# Trail-Traffic-Counter-Board-v10.net
KiCad netlist of a schematic drawn in EAGLE
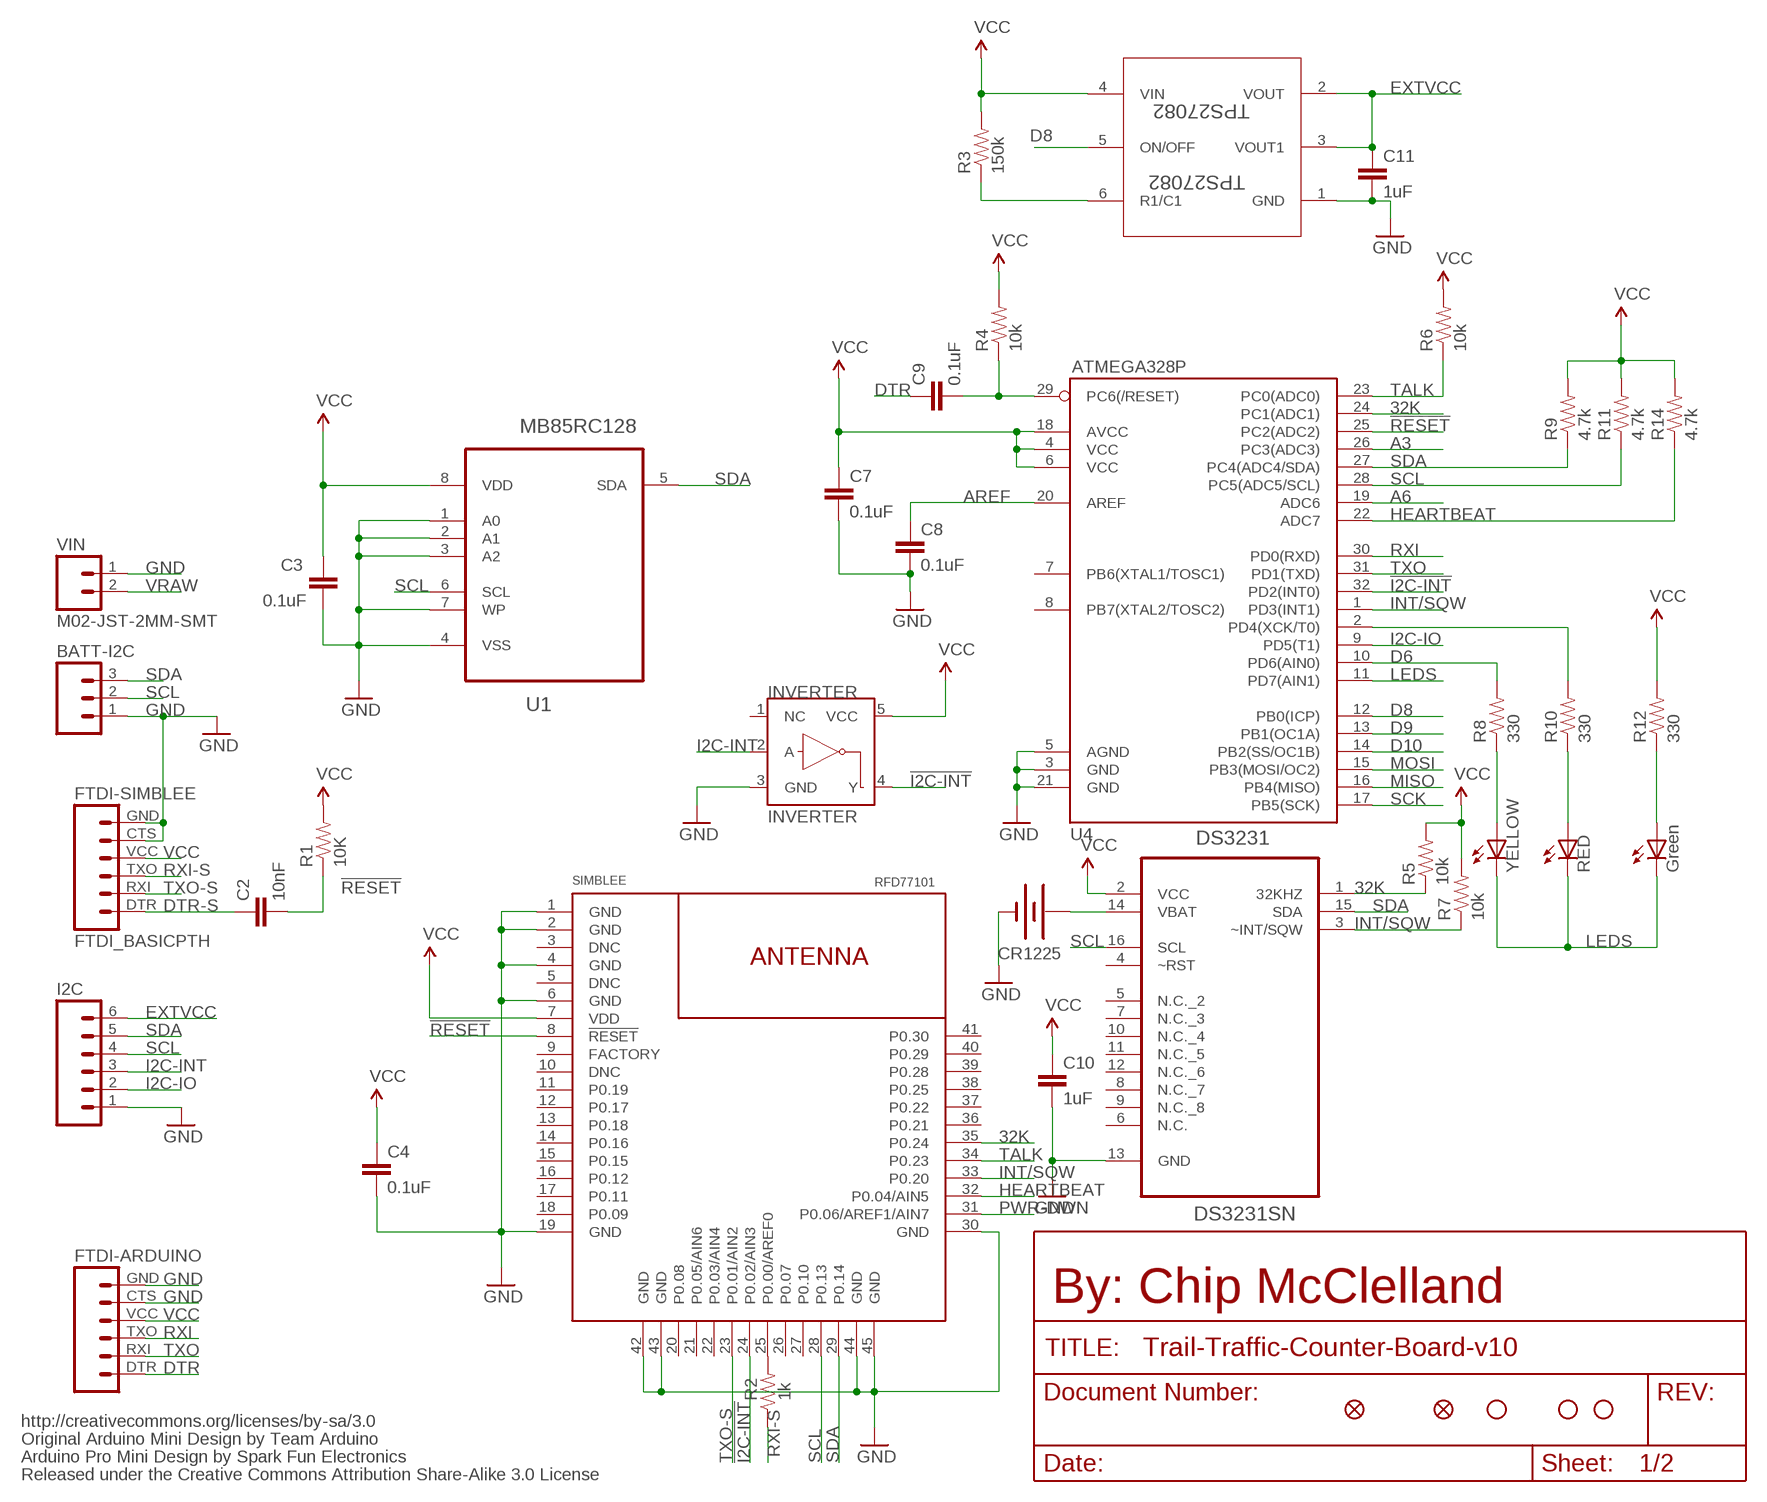
[diagram p0: schematic, sheet 1]
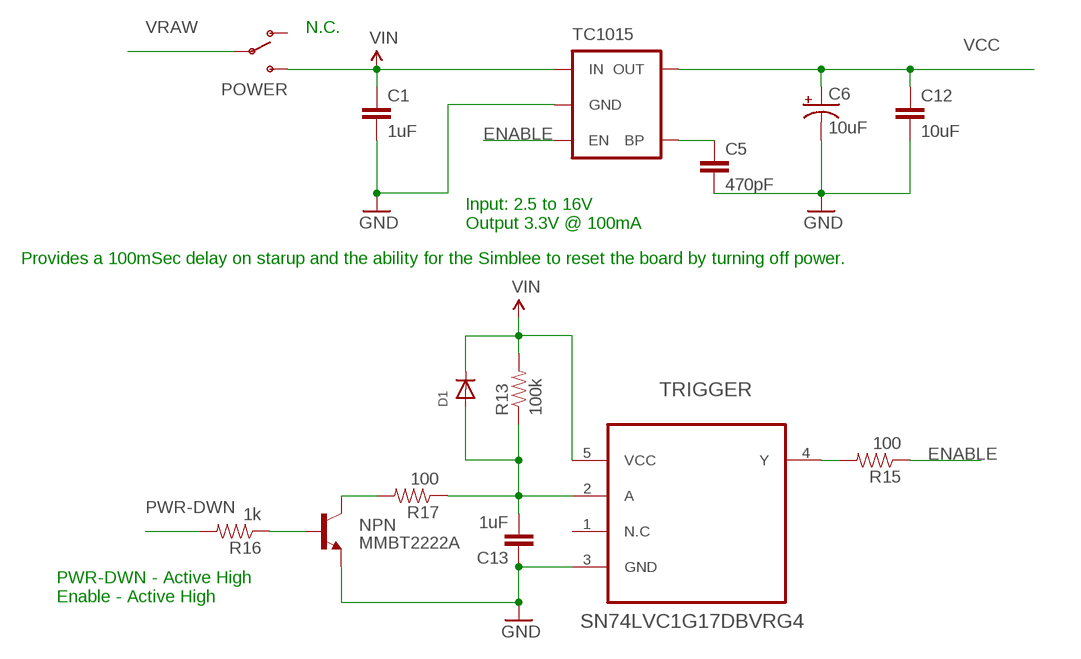
[diagram p1: schematic, sheet 2]

(export (version "E")
  (design (tool "Eeschema 10.0.6"))
  (components
    (comp (ref "C1")
      (value "1uF")
      (footprint "eagle-import:0805")
      (libsource (lib "eagle-import") (part "SparkFun-Passives_CAP0805"))
    )
    (comp (ref "C5")
      (value "470pF")
      (footprint "eagle-import:0805")
      (libsource (lib "eagle-import") (part "SparkFun-Passives_CAP0805"))
    )
    (comp (ref "C6")
      (value "10uF")
      (footprint "eagle-import:EIA3216")
      (libsource (lib "eagle-import") (part "CAP_POL1206"))
    )
    (comp (ref "C12")
      (value "10uF")
      (footprint "eagle-import:0805")
      (libsource (lib "eagle-import") (part "SparkFun-Passives_CAP0805"))
    )
    (comp (ref "C13")
      (value "1uF")
      (footprint "eagle-import:0805")
      (libsource (lib "eagle-import") (part "CAP0805"))
    )
    (comp (ref "D1")
      (value "DIODESOD-523")
      (footprint "eagle-import:SOD-523")
      (libsource (lib "eagle-import") (part "DIODESOD-523"))
    )
    (comp (ref "NPN")
      (value "MMBT2222A")
      (footprint "eagle-import:SOT23-3")
      (libsource (lib "eagle-import") (part "TRANSISTOR_NPNMMBT2222A"))
    )
    (comp (ref "POWER")
      (value "SWITCH-SPDTPTH")
      (footprint "eagle-import:SWITCH-SPDT")
      (libsource (lib "eagle-import") (part "SWITCH-SPDTPTH"))
    )
    (comp (ref "R13")
      (value "100k")
      (footprint "eagle-import:0805")
      (libsource (lib "eagle-import") (part "RESISTOR0805-RES"))
    )
    (comp (ref "R15")
      (value "100")
      (footprint "eagle-import:0805")
      (libsource (lib "eagle-import") (part "RESISTOR0805-RES"))
    )
    (comp (ref "R16")
      (value "1k")
      (footprint "eagle-import:0805")
      (libsource (lib "eagle-import") (part "RESISTOR0805-RES"))
    )
    (comp (ref "R17")
      (value "100")
      (footprint "eagle-import:0805")
      (libsource (lib "eagle-import") (part "RESISTOR0805-RES"))
    )
    (comp (ref "TC1015")
      (value "MIC52053.3V")
      (footprint "eagle-import:SOT23-5")
      (libsource (lib "eagle-import") (part "MIC52053.3V"))
    )
    (comp (ref "TRIGGER")
      (value "SN74LVC1G17DBVRG4")
      (footprint "eagle-import:SOT95P280X145-5N")
      (libsource (lib "eagle-import") (part "SN74LVC1G17DBVRG4"))
    )
    (comp (ref "ATMEGA328P")
      (value "U4")
      (footprint "eagle-import:TQFP32-08")
      (libsource (lib "eagle-import") (part "ATMEGA168"))
    )
    (comp (ref "BATT-I2C")
      (value "M03LOCK")
      (footprint "eagle-import:1X03_LOCK")
      (libsource (lib "eagle-import") (part "M03LOCK"))
    )
    (comp (ref "C2")
      (value "10nF")
      (footprint "eagle-import:0805")
      (libsource (lib "eagle-import") (part "SparkFun-Passives_CAP0805"))
    )
    (comp (ref "C3")
      (value "0.1uF")
      (footprint "eagle-import:0805")
      (libsource (lib "eagle-import") (part "CAP0805"))
    )
    (comp (ref "C4")
      (value "0.1uF")
      (footprint "eagle-import:0805")
      (libsource (lib "eagle-import") (part "CAP0805"))
    )
    (comp (ref "C7")
      (value "0.1uF")
      (footprint "eagle-import:0805")
      (libsource (lib "eagle-import") (part "CAP0805"))
    )
    (comp (ref "C8")
      (value "0.1uF")
      (footprint "eagle-import:0805")
      (libsource (lib "eagle-import") (part "CAP0805"))
    )
    (comp (ref "C9")
      (value "0.1uF")
      (footprint "eagle-import:0805")
      (libsource (lib "eagle-import") (part "CAP0805"))
    )
    (comp (ref "C10")
      (value "1uF")
      (footprint "eagle-import:0805")
      (libsource (lib "eagle-import") (part "CAP0805"))
    )
    (comp (ref "C11")
      (value "1uF")
      (footprint "eagle-import:0805")
      (libsource (lib "eagle-import") (part "CAP0805"))
    )
    (comp (ref "CR1225")
      (value "BATTERY12MM")
      (footprint "eagle-import:BATTCON_12MM")
      (libsource (lib "eagle-import") (part "BATTERY12MM"))
    )
    (comp (ref "DS3231")
      (value "DS3231SN")
      (footprint "eagle-import:SOIC127P1032X265-16N")
      (fields (field (name "MPN") "DS3231SN#"))
      (libsource (lib "eagle-import") (part "DS3231SN"))
    )
    (comp (ref "FID1")
      (value "FIDUCIALUFIDUCIAL")
      (footprint "eagle-import:MICRO-FIDUCIAL")
      (libsource (lib "eagle-import") (part "FIDUCIALUFIDUCIAL"))
    )
    (comp (ref "FID2")
      (value "FIDUCIALUFIDUCIAL")
      (footprint "eagle-import:MICRO-FIDUCIAL")
      (libsource (lib "eagle-import") (part "FIDUCIALUFIDUCIAL"))
    )
    (comp (ref "FTDI-ARDUINO")
      (value "FTDI Basic")
      (footprint "eagle-import:FTDI_BASIC")
      (libsource (lib "eagle-import") (part "FTDI_BASICPTH"))
    )
    (comp (ref "FTDI-SIMBLEE")
      (value "FTDI_BASICPTH")
      (footprint "eagle-import:FTDI_BASIC")
      (libsource (lib "eagle-import") (part "FTDI_BASICPTH"))
    )
    (comp (ref "I2C")
      (value "M06LOCK")
      (footprint "eagle-import:1X06_LOCK")
      (libsource (lib "eagle-import") (part "M06LOCK"))
    )
    (comp (ref "INVERTER")
      (value "INVERTER")
      (footprint "eagle-import:SOT23-5")
      (libsource (lib "eagle-import") (part "INVERTER"))
    )
    (comp (ref "JP6")
      (value "STAND-OFF")
      (footprint "eagle-import:STAND-OFF")
      (libsource (lib "eagle-import") (part "STAND-OFF"))
    )
    (comp (ref "JP7")
      (value "STAND-OFF")
      (footprint "eagle-import:STAND-OFF")
      (libsource (lib "eagle-import") (part "STAND-OFF"))
    )
    (comp (ref "JP8")
      (value "STAND-OFF")
      (footprint "eagle-import:STAND-OFF")
      (libsource (lib "eagle-import") (part "STAND-OFF"))
    )
    (comp (ref "LED1")
      (value "YELLOW")
      (footprint "eagle-import:CHIPLED_0805")
      (libsource (lib "eagle-import") (part "LEDCHIPLED_0805"))
    )
    (comp (ref "LED2")
      (value "RED")
      (footprint "eagle-import:CHIPLED_0805")
      (libsource (lib "eagle-import") (part "LEDCHIPLED_0805"))
    )
    (comp (ref "MB85RC128")
      (value "U1")
      (footprint "eagle-import:SOIC127P600X175-8N")
      (fields (field (name "MPN") "MB85RC128PNF-G-JNE1"))
      (libsource (lib "eagle-import") (part "MB85RC128PNF-G-JNE1"))
    )
    (comp (ref "PWR")
      (value "Green")
      (footprint "eagle-import:CHIPLED_0805")
      (libsource (lib "eagle-import") (part "LEDCHIPLED_0805"))
    )
    (comp (ref "R1")
      (value "10K")
      (footprint "eagle-import:0805")
      (libsource (lib "eagle-import") (part "RESISTOR0805-RES"))
    )
    (comp (ref "R2")
      (value "1k")
      (footprint "eagle-import:0805")
      (libsource (lib "eagle-import") (part "RESISTOR0805-RES"))
    )
    (comp (ref "R3")
      (value "150k")
      (footprint "eagle-import:0805")
      (libsource (lib "eagle-import") (part "RESISTOR0805-RES"))
    )
    (comp (ref "R4")
      (value "10k")
      (footprint "eagle-import:0805")
      (libsource (lib "eagle-import") (part "RESISTOR0805-RES"))
    )
    (comp (ref "R5")
      (value "10k")
      (footprint "eagle-import:0805")
      (libsource (lib "eagle-import") (part "RESISTOR0805-RES"))
    )
    (comp (ref "R6")
      (value "10k")
      (footprint "eagle-import:0805")
      (libsource (lib "eagle-import") (part "RESISTOR0805-RES"))
    )
    (comp (ref "R7")
      (value "10k")
      (footprint "eagle-import:0805")
      (libsource (lib "eagle-import") (part "RESISTOR0805-RES"))
    )
    (comp (ref "R8")
      (value "330")
      (footprint "eagle-import:0603-RES")
      (libsource (lib "eagle-import") (part "RESISTOR0603"))
    )
    (comp (ref "R9")
      (value "4.7k")
      (footprint "eagle-import:0805")
      (libsource (lib "eagle-import") (part "SparkFun-Resistors_RESISTOR0805-RES"))
    )
    (comp (ref "R10")
      (value "330")
      (footprint "eagle-import:0603-RES")
      (libsource (lib "eagle-import") (part "RESISTOR0603"))
    )
    (comp (ref "R11")
      (value "4.7k")
      (footprint "eagle-import:0805")
      (libsource (lib "eagle-import") (part "SparkFun-Resistors_RESISTOR0805-RES"))
    )
    (comp (ref "R12")
      (value "330")
      (footprint "eagle-import:0603-RES")
      (libsource (lib "eagle-import") (part "RESISTOR0603"))
    )
    (comp (ref "R14")
      (value "4.7k")
      (footprint "eagle-import:0805")
      (libsource (lib "eagle-import") (part "SparkFun-Resistors_RESISTOR0805-RES"))
    )
    (comp (ref "SIMBLEE")
      (value "RFD77101")
      (footprint "eagle-import:RFD77101")
      (libsource (lib "eagle-import") (part "RFD77101"))
    )
    (comp (ref "TPS27082")
      (value "TPS27082")
      (footprint "eagle-import:TSOT-23")
      (libsource (lib "eagle-import") (part "TPS27082"))
    )
    (comp (ref "VIN")
      (value "M02-JST-2MM-SMT")
      (footprint "eagle-import:JST-2-SMD")
      (libsource (lib "eagle-import") (part "M02-JST-2MM-SMT"))
    )
  )
  (nets
    (net (code "1") (name "32K") (class "Default")
      (node (ref "ATMEGA328P") (pin "24") (pinfunction "PC1(ADC1)_24") (pintype "bidirectional"))
      (node (ref "DS3231") (pin "1") (pinfunction "32KHZ_1") (pintype "output"))
      (node (ref "R5") (pin "1") (pinfunction "1_1") (pintype "passive"))
      (node (ref "SIMBLEE") (pin "35") (pinfunction "P0.24_35") (pintype "bidirectional"))
    )
    (net (code "2") (name "A3") (class "Default")
      (node (ref "ATMEGA328P") (pin "26") (pinfunction "PC3(ADC3)_26") (pintype "bidirectional"))
    )
    (net (code "3") (name "A6") (class "Default")
      (node (ref "ATMEGA328P") (pin "19") (pinfunction "ADC6_19") (pintype "bidirectional"))
    )
    (net (code "4") (name "AREF") (class "Default")
      (node (ref "ATMEGA328P") (pin "20") (pinfunction "AREF_20") (pintype "bidirectional"))
      (node (ref "C8") (pin "1") (pinfunction "1_1") (pintype "passive"))
    )
    (net (code "5") (name "D6") (class "Default")
      (node (ref "ATMEGA328P") (pin "10") (pinfunction "PD6(AIN0)_10") (pintype "bidirectional"))
      (node (ref "R8") (pin "2") (pinfunction "2_2") (pintype "passive"))
    )
    (net (code "6") (name "D8") (class "Default")
      (node (ref "ATMEGA328P") (pin "12") (pinfunction "PB0(ICP)_12") (pintype "bidirectional"))
      (node (ref "TPS27082") (pin "5") (pinfunction "ON/OFF_5") (pintype "bidirectional"))
    )
    (net (code "7") (name "D9") (class "Default")
      (node (ref "ATMEGA328P") (pin "13") (pinfunction "PB1(OC1A)_13") (pintype "bidirectional"))
    )
    (net (code "8") (name "D10") (class "Default")
      (node (ref "ATMEGA328P") (pin "14") (pinfunction "PB2(SS/OC1B)_14") (pintype "bidirectional"))
    )
    (net (code "9") (name "DTR") (class "Default")
      (node (ref "C9") (pin "1") (pinfunction "1_1") (pintype "passive"))
      (node (ref "FTDI-ARDUINO") (pin "DTR") (pinfunction "1_DTR") (pintype "passive"))
    )
    (net (code "10") (name "DTR-S") (class "Default")
      (node (ref "C2") (pin "1") (pinfunction "1_1") (pintype "passive"))
      (node (ref "FTDI-SIMBLEE") (pin "DTR") (pinfunction "1_DTR") (pintype "passive"))
    )
    (net (code "11") (name "ENABLE") (class "Default")
      (node (ref "R15") (pin "1") (pinfunction "1_1") (pintype "passive"))
      (node (ref "TC1015") (pin "3") (pinfunction "EN_3") (pintype "input"))
    )
    (net (code "12") (name "EXTVCC") (class "Default")
      (node (ref "C11") (pin "1") (pinfunction "1_1") (pintype "passive"))
      (node (ref "I2C") (pin "6") (pinfunction "6_6") (pintype "passive"))
      (node (ref "TPS27082") (pin "2") (pinfunction "VOUT_2") (pintype "power_in"))
      (node (ref "TPS27082") (pin "3") (pinfunction "VOUT1_3") (pintype "input"))
    )
    (net (code "13") (name "GND") (class "Default")
      (node (ref "ATMEGA328P") (pin "21") (pinfunction "GND_21") (pintype "bidirectional"))
      (node (ref "ATMEGA328P") (pin "3") (pinfunction "GND_3") (pintype "bidirectional"))
      (node (ref "ATMEGA328P") (pin "5") (pinfunction "AGND_5") (pintype "bidirectional"))
      (node (ref "BATT-I2C") (pin "1") (pinfunction "1_1") (pintype "passive"))
      (node (ref "C1") (pin "2") (pinfunction "2_2") (pintype "passive"))
      (node (ref "C10") (pin "2") (pinfunction "2_2") (pintype "passive"))
      (node (ref "C11") (pin "2") (pinfunction "2_2") (pintype "passive"))
      (node (ref "C12") (pin "2") (pinfunction "2_2") (pintype "passive"))
      (node (ref "C13") (pin "1") (pinfunction "1_1") (pintype "passive"))
      (node (ref "C3") (pin "2") (pinfunction "2_2") (pintype "passive"))
      (node (ref "C4") (pin "2") (pinfunction "2_2") (pintype "passive"))
      (node (ref "C5") (pin "2") (pinfunction "2_2") (pintype "passive"))
      (node (ref "C6") (pin "C") (pinfunction "-_C") (pintype "passive"))
      (node (ref "C7") (pin "2") (pinfunction "2_2") (pintype "passive"))
      (node (ref "C8") (pin "2") (pinfunction "2_2") (pintype "passive"))
      (node (ref "CR1225") (pin "GND") (pinfunction "-_GND") (pintype "power_in"))
      (node (ref "DS3231") (pin "13") (pinfunction "GND_13") (pintype "passive"))
      (node (ref "FTDI-ARDUINO") (pin "CTS") (pinfunction "5_CTS") (pintype "passive"))
      (node (ref "FTDI-ARDUINO") (pin "GND") (pinfunction "6_GND") (pintype "passive"))
      (node (ref "FTDI-SIMBLEE") (pin "CTS") (pinfunction "5_CTS") (pintype "passive"))
      (node (ref "FTDI-SIMBLEE") (pin "GND") (pinfunction "6_GND") (pintype "passive"))
      (node (ref "I2C") (pin "1") (pinfunction "1_1") (pintype "passive"))
      (node (ref "INVERTER") (pin "3") (pinfunction "GND_3") (pintype "bidirectional"))
      (node (ref "MB85RC128") (pin "1") (pinfunction "A0_1") (pintype "input"))
      (node (ref "MB85RC128") (pin "2") (pinfunction "A1_2") (pintype "input"))
      (node (ref "MB85RC128") (pin "3") (pinfunction "A2_3") (pintype "input"))
      (node (ref "MB85RC128") (pin "4") (pinfunction "VSS_4") (pintype "passive"))
      (node (ref "MB85RC128") (pin "7") (pinfunction "WP_7") (pintype "input"))
      (node (ref "NPN") (pin "2") (pinfunction "E_2") (pintype "passive"))
      (node (ref "SIMBLEE") (pin "1") (pinfunction "GND_1") (pintype "power_in"))
      (node (ref "SIMBLEE") (pin "19") (pinfunction "GND_19") (pintype "power_in"))
      (node (ref "SIMBLEE") (pin "2") (pinfunction "GND_2") (pintype "power_in"))
      (node (ref "SIMBLEE") (pin "30") (pinfunction "GND_30") (pintype "power_in"))
      (node (ref "SIMBLEE") (pin "4") (pinfunction "GND_4") (pintype "power_in"))
      (node (ref "SIMBLEE") (pin "42") (pinfunction "GND_42") (pintype "power_in"))
      (node (ref "SIMBLEE") (pin "43") (pinfunction "GND_43") (pintype "power_in"))
      (node (ref "SIMBLEE") (pin "44") (pinfunction "GND_44") (pintype "power_in"))
      (node (ref "SIMBLEE") (pin "45") (pinfunction "GND_45") (pintype "power_in"))
      (node (ref "SIMBLEE") (pin "6") (pinfunction "GND_6") (pintype "power_in"))
      (node (ref "TC1015") (pin "2") (pinfunction "GND_2") (pintype "input"))
      (node (ref "TPS27082") (pin "1") (pinfunction "GND_1") (pintype "power_in"))
      (node (ref "TRIGGER") (pin "3") (pinfunction "GND_3") (pintype "passive"))
      (node (ref "VIN") (pin "1") (pinfunction "2_1") (pintype "passive"))
    )
    (net (code "14") (name "HEARTBEAT") (class "Default")
      (node (ref "ATMEGA328P") (pin "22") (pinfunction "ADC7_22") (pintype "bidirectional"))
      (node (ref "R14") (pin "1") (pinfunction "1_1") (pintype "passive"))
      (node (ref "SIMBLEE") (pin "32") (pinfunction "P0.04/AIN5_32") (pintype "bidirectional"))
    )
    (net (code "15") (name "I2C-INT") (class "Default")
      (node (ref "I2C") (pin "3") (pinfunction "3_3") (pintype "passive"))
      (node (ref "INVERTER") (pin "2") (pinfunction "A_2") (pintype "bidirectional"))
    )
    (net (code "16") (name "I2C-IO") (class "Default")
      (node (ref "ATMEGA328P") (pin "9") (pinfunction "PD5(T1)_9") (pintype "bidirectional"))
      (node (ref "I2C") (pin "2") (pinfunction "2_2") (pintype "passive"))
    )
    (net (code "17") (name "INT{slash}SQW") (class "Default")
      (node (ref "ATMEGA328P") (pin "1") (pinfunction "PD3(INT1)_1") (pintype "bidirectional"))
      (node (ref "DS3231") (pin "3") (pinfunction "~{INT/SQW}_3") (pintype "output"))
      (node (ref "R7") (pin "1") (pinfunction "1_1") (pintype "passive"))
      (node (ref "SIMBLEE") (pin "33") (pinfunction "P0.20_33") (pintype "bidirectional"))
    )
    (net (code "18") (name "LEDS") (class "Default")
      (node (ref "ATMEGA328P") (pin "11") (pinfunction "PD7(AIN1)_11") (pintype "bidirectional"))
      (node (ref "LED1") (pin "C") (pinfunction "C_C") (pintype "passive"))
      (node (ref "LED2") (pin "C") (pinfunction "C_C") (pintype "passive"))
      (node (ref "PWR") (pin "C") (pinfunction "C_C") (pintype "passive"))
    )
    (net (code "19") (name "MISO") (class "Default")
      (node (ref "ATMEGA328P") (pin "16") (pinfunction "PB4(MISO)_16") (pintype "bidirectional"))
    )
    (net (code "20") (name "MOSI") (class "Default")
      (node (ref "ATMEGA328P") (pin "15") (pinfunction "PB3(MOSI/OC2)_15") (pintype "bidirectional"))
    )
    (net (code "21") (name "Net-(ATMEGA328P-PC6({slash}RESET))") (class "Default")
      (node (ref "ATMEGA328P") (pin "29") (pinfunction "PC6(/RESET)_29") (pintype "bidirectional"))
      (node (ref "C9") (pin "2") (pinfunction "2_2") (pintype "passive"))
      (node (ref "R4") (pin "1") (pinfunction "1_1") (pintype "passive"))
    )
    (net (code "22") (name "Net-(ATMEGA328P-PD4(XCK{slash}T0))") (class "Default")
      (node (ref "ATMEGA328P") (pin "2") (pinfunction "PD4(XCK/T0)_2") (pintype "bidirectional"))
      (node (ref "R10") (pin "2") (pinfunction "2_2") (pintype "passive"))
    )
    (net (code "23") (name "Net-(CR1225-+)") (class "Default")
      (node (ref "CR1225") (pin "PWR@1") (pinfunction "+_PWR@1") (pintype "power_in"))
      (node (ref "DS3231") (pin "14") (pinfunction "VBAT_14") (pintype "power_in"))
    )
    (net (code "24") (name "Net-(LED1-PadA)") (class "Default")
      (node (ref "LED1") (pin "A") (pinfunction "A_A") (pintype "passive"))
      (node (ref "R8") (pin "1") (pinfunction "1_1") (pintype "passive"))
    )
    (net (code "25") (name "Net-(LED2-PadA)") (class "Default")
      (node (ref "LED2") (pin "A") (pinfunction "A_A") (pintype "passive"))
      (node (ref "R10") (pin "1") (pinfunction "1_1") (pintype "passive"))
    )
    (net (code "26") (name "Net-(NPN-B)") (class "Default")
      (node (ref "NPN") (pin "1") (pinfunction "B_1") (pintype "passive"))
      (node (ref "R16") (pin "1") (pinfunction "1_1") (pintype "passive"))
    )
    (net (code "27") (name "Net-(NPN-C)") (class "Default")
      (node (ref "NPN") (pin "3") (pinfunction "C_3") (pintype "passive"))
      (node (ref "R17") (pin "2") (pinfunction "2_2") (pintype "passive"))
    )
    (net (code "28") (name "Net-(PWR-PadA)") (class "Default")
      (node (ref "PWR") (pin "A") (pinfunction "A_A") (pintype "passive"))
      (node (ref "R12") (pin "1") (pinfunction "1_1") (pintype "passive"))
    )
    (net (code "29") (name "Net-(SIMBLEE-P0.00{slash}AREF0)") (class "Default")
      (node (ref "R2") (pin "2") (pinfunction "2_2") (pintype "passive"))
      (node (ref "SIMBLEE") (pin "25") (pinfunction "P0.00/AREF0_25") (pintype "bidirectional"))
    )
    (net (code "30") (name "Net-(TC1015-BP)") (class "Default")
      (node (ref "C5") (pin "1") (pinfunction "1_1") (pintype "passive"))
      (node (ref "TC1015") (pin "4") (pinfunction "BP_4") (pintype "input"))
    )
    (net (code "31") (name "Net-(TPS27082-R1{slash}C1)") (class "Default")
      (node (ref "R3") (pin "1") (pinfunction "1_1") (pintype "passive"))
      (node (ref "TPS27082") (pin "6") (pinfunction "R1/C1_6") (pintype "power_in"))
    )
    (net (code "32") (name "Net-(TRIGGER-A)") (class "Default")
      (node (ref "C13") (pin "2") (pinfunction "2_2") (pintype "passive"))
      (node (ref "D1") (pin "A") (pinfunction "A_A") (pintype "passive"))
      (node (ref "R13") (pin "1") (pinfunction "1_1") (pintype "passive"))
      (node (ref "R17") (pin "1") (pinfunction "1_1") (pintype "passive"))
      (node (ref "TRIGGER") (pin "2") (pinfunction "A_2") (pintype "input"))
    )
    (net (code "33") (name "Net-(TRIGGER-Y)") (class "Default")
      (node (ref "R15") (pin "2") (pinfunction "2_2") (pintype "passive"))
      (node (ref "TRIGGER") (pin "4") (pinfunction "Y_4") (pintype "output"))
    )
    (net (code "34") (name "PWR-DWN") (class "Default")
      (node (ref "R16") (pin "2") (pinfunction "2_2") (pintype "passive"))
      (node (ref "SIMBLEE") (pin "31") (pinfunction "P0.06/AREF1/AIN7_31") (pintype "bidirectional"))
    )
    (net (code "35") (name "RXI") (class "Default")
      (node (ref "ATMEGA328P") (pin "30") (pinfunction "PD0(RXD)_30") (pintype "bidirectional"))
      (node (ref "FTDI-ARDUINO") (pin "TXO") (pinfunction "3_TXO") (pintype "passive"))
    )
    (net (code "36") (name "RXI-S") (class "Default")
      (node (ref "FTDI-SIMBLEE") (pin "TXO") (pinfunction "3_TXO") (pintype "passive"))
      (node (ref "R2") (pin "1") (pinfunction "1_1") (pintype "passive"))
    )
    (net (code "37") (name "SCK") (class "Default")
      (node (ref "ATMEGA328P") (pin "17") (pinfunction "PB5(SCK)_17") (pintype "bidirectional"))
    )
    (net (code "38") (name "SCL") (class "Default")
      (node (ref "ATMEGA328P") (pin "28") (pinfunction "PC5(ADC5/SCL)_28") (pintype "bidirectional"))
      (node (ref "BATT-I2C") (pin "2") (pinfunction "2_2") (pintype "passive"))
      (node (ref "DS3231") (pin "16") (pinfunction "SCL_16") (pintype "input"))
      (node (ref "I2C") (pin "4") (pinfunction "4_4") (pintype "passive"))
      (node (ref "MB85RC128") (pin "6") (pinfunction "SCL_6") (pintype "input"))
      (node (ref "R11") (pin "1") (pinfunction "1_1") (pintype "passive"))
      (node (ref "SIMBLEE") (pin "28") (pinfunction "P0.13_28") (pintype "bidirectional"))
    )
    (net (code "39") (name "SDA") (class "Default")
      (node (ref "ATMEGA328P") (pin "27") (pinfunction "PC4(ADC4/SDA)_27") (pintype "bidirectional"))
      (node (ref "BATT-I2C") (pin "3") (pinfunction "3_3") (pintype "passive"))
      (node (ref "DS3231") (pin "15") (pinfunction "SDA_15") (pintype "bidirectional"))
      (node (ref "I2C") (pin "5") (pinfunction "5_5") (pintype "passive"))
      (node (ref "MB85RC128") (pin "5") (pinfunction "SDA_5") (pintype "bidirectional"))
      (node (ref "R9") (pin "1") (pinfunction "1_1") (pintype "passive"))
      (node (ref "SIMBLEE") (pin "29") (pinfunction "P0.14_29") (pintype "bidirectional"))
    )
    (net (code "40") (name "TALK") (class "Default")
      (node (ref "ATMEGA328P") (pin "23") (pinfunction "PC0(ADC0)_23") (pintype "bidirectional"))
      (node (ref "R6") (pin "1") (pinfunction "1_1") (pintype "passive"))
      (node (ref "SIMBLEE") (pin "34") (pinfunction "P0.23_34") (pintype "bidirectional"))
    )
    (net (code "41") (name "TXO") (class "Default")
      (node (ref "ATMEGA328P") (pin "31") (pinfunction "PD1(TXD)_31") (pintype "bidirectional"))
      (node (ref "FTDI-ARDUINO") (pin "RXI") (pinfunction "2_RXI") (pintype "passive"))
    )
    (net (code "42") (name "TXO-S") (class "Default")
      (node (ref "FTDI-SIMBLEE") (pin "RXI") (pinfunction "2_RXI") (pintype "passive"))
      (node (ref "SIMBLEE") (pin "23") (pinfunction "P0.01/AIN2_23") (pintype "bidirectional"))
    )
    (net (code "43") (name "VCC") (class "Default")
      (node (ref "ATMEGA328P") (pin "18") (pinfunction "AVCC_18") (pintype "bidirectional"))
      (node (ref "ATMEGA328P") (pin "4") (pinfunction "VCC_4") (pintype "bidirectional"))
      (node (ref "ATMEGA328P") (pin "6") (pinfunction "VCC_6") (pintype "bidirectional"))
      (node (ref "C10") (pin "1") (pinfunction "1_1") (pintype "passive"))
      (node (ref "C12") (pin "1") (pinfunction "1_1") (pintype "passive"))
      (node (ref "C3") (pin "1") (pinfunction "1_1") (pintype "passive"))
      (node (ref "C4") (pin "1") (pinfunction "1_1") (pintype "passive"))
      (node (ref "C6") (pin "A") (pinfunction "+_A") (pintype "passive"))
      (node (ref "C7") (pin "1") (pinfunction "1_1") (pintype "passive"))
      (node (ref "DS3231") (pin "2") (pinfunction "VCC_2") (pintype "power_in"))
      (node (ref "FTDI-ARDUINO") (pin "VCC") (pinfunction "4_VCC") (pintype "passive"))
      (node (ref "FTDI-SIMBLEE") (pin "VCC") (pinfunction "4_VCC") (pintype "passive"))
      (node (ref "INVERTER") (pin "5") (pinfunction "VCC_5") (pintype "bidirectional"))
      (node (ref "MB85RC128") (pin "8") (pinfunction "VDD_8") (pintype "power_in"))
      (node (ref "R1") (pin "2") (pinfunction "2_2") (pintype "passive"))
      (node (ref "R11") (pin "2") (pinfunction "2_2") (pintype "passive"))
      (node (ref "R12") (pin "2") (pinfunction "2_2") (pintype "passive"))
      (node (ref "R14") (pin "2") (pinfunction "2_2") (pintype "passive"))
      (node (ref "R3") (pin "2") (pinfunction "2_2") (pintype "passive"))
      (node (ref "R4") (pin "2") (pinfunction "2_2") (pintype "passive"))
      (node (ref "R5") (pin "2") (pinfunction "2_2") (pintype "passive"))
      (node (ref "R6") (pin "2") (pinfunction "2_2") (pintype "passive"))
      (node (ref "R7") (pin "2") (pinfunction "2_2") (pintype "passive"))
      (node (ref "R9") (pin "2") (pinfunction "2_2") (pintype "passive"))
      (node (ref "SIMBLEE") (pin "7") (pinfunction "VDD_7") (pintype "power_in"))
      (node (ref "TC1015") (pin "5") (pinfunction "OUT_5") (pintype "passive"))
      (node (ref "TPS27082") (pin "4") (pinfunction "VIN_4") (pintype "input"))
    )
    (net (code "44") (name "VIN") (class "Default")
      (node (ref "C1") (pin "1") (pinfunction "1_1") (pintype "passive"))
      (node (ref "D1") (pin "K") (pinfunction "C_K") (pintype "passive"))
      (node (ref "POWER") (pin "3") (pinfunction "S_3") (pintype "passive"))
      (node (ref "R13") (pin "2") (pinfunction "2_2") (pintype "passive"))
      (node (ref "TC1015") (pin "1") (pinfunction "IN_1") (pintype "input"))
      (node (ref "TRIGGER") (pin "5") (pinfunction "VCC_5") (pintype "power_in"))
    )
    (net (code "45") (name "VRAW") (class "Default")
      (node (ref "POWER") (pin "2") (pinfunction "P_2") (pintype "passive"))
      (node (ref "VIN") (pin "2") (pinfunction "1_2") (pintype "passive"))
    )
    (net (code "46") (name "unconnected-(ATMEGA328P-PB6(XTAL1{slash}TOSC1)-Pad7)") (class "Default")
      (node (ref "ATMEGA328P") (pin "7") (pinfunction "PB6(XTAL1/TOSC1)_7") (pintype "bidirectional"))
    )
    (net (code "47") (name "unconnected-(ATMEGA328P-PB7(XTAL2{slash}TOSC2)-Pad8)") (class "Default")
      (node (ref "ATMEGA328P") (pin "8") (pinfunction "PB7(XTAL2/TOSC2)_8") (pintype "bidirectional"))
    )
    (net (code "48") (name "unconnected-(DS3231-N.C.-Pad6)") (class "Default")
      (node (ref "DS3231") (pin "6") (pinfunction "N.C._6") (pintype "no_connect"))
    )
    (net (code "49") (name "unconnected-(DS3231-N.C._2-Pad5)") (class "Default")
      (node (ref "DS3231") (pin "5") (pinfunction "N.C._2_5") (pintype "no_connect"))
    )
    (net (code "50") (name "unconnected-(DS3231-N.C._3-Pad7)") (class "Default")
      (node (ref "DS3231") (pin "7") (pinfunction "N.C._3_7") (pintype "no_connect"))
    )
    (net (code "51") (name "unconnected-(DS3231-N.C._4-Pad10)") (class "Default")
      (node (ref "DS3231") (pin "10") (pinfunction "N.C._4_10") (pintype "no_connect"))
    )
    (net (code "52") (name "unconnected-(DS3231-N.C._5-Pad11)") (class "Default")
      (node (ref "DS3231") (pin "11") (pinfunction "N.C._5_11") (pintype "no_connect"))
    )
    (net (code "53") (name "unconnected-(DS3231-N.C._6-Pad12)") (class "Default")
      (node (ref "DS3231") (pin "12") (pinfunction "N.C._6_12") (pintype "no_connect"))
    )
    (net (code "54") (name "unconnected-(DS3231-N.C._7-Pad8)") (class "Default")
      (node (ref "DS3231") (pin "8") (pinfunction "N.C._7_8") (pintype "no_connect"))
    )
    (net (code "55") (name "unconnected-(DS3231-N.C._8-Pad9)") (class "Default")
      (node (ref "DS3231") (pin "9") (pinfunction "N.C._8_9") (pintype "no_connect"))
    )
    (net (code "56") (name "unconnected-(DS3231-~{RST}-Pad4)") (class "Default")
      (node (ref "DS3231") (pin "4") (pinfunction "~{RST}_4") (pintype "bidirectional"))
    )
    (net (code "57") (name "unconnected-(INVERTER-NC-Pad1)") (class "Default")
      (node (ref "INVERTER") (pin "1") (pinfunction "NC_1") (pintype "bidirectional"))
    )
    (net (code "58") (name "unconnected-(POWER-O-Pad1)") (class "Default")
      (node (ref "POWER") (pin "1") (pinfunction "O_1") (pintype "passive"))
    )
    (net (code "59") (name "unconnected-(SIMBLEE-DNC-Pad3)") (class "Default")
      (node (ref "SIMBLEE") (pin "3") (pinfunction "DNC_3") (pintype "no_connect"))
    )
    (net (code "60") (name "unconnected-(SIMBLEE-DNC-Pad5)") (class "Default")
      (node (ref "SIMBLEE") (pin "5") (pinfunction "DNC_5") (pintype "no_connect"))
    )
    (net (code "61") (name "unconnected-(SIMBLEE-DNC-Pad10)") (class "Default")
      (node (ref "SIMBLEE") (pin "10") (pinfunction "DNC_10") (pintype "no_connect"))
    )
    (net (code "62") (name "unconnected-(SIMBLEE-FACTORY-Pad9)") (class "Default")
      (node (ref "SIMBLEE") (pin "9") (pinfunction "FACTORY_9") (pintype "no_connect"))
    )
    (net (code "63") (name "unconnected-(SIMBLEE-P0.03{slash}AIN4-Pad22)") (class "Default")
      (node (ref "SIMBLEE") (pin "22") (pinfunction "P0.03/AIN4_22") (pintype "bidirectional"))
    )
    (net (code "64") (name "unconnected-(SIMBLEE-P0.05{slash}AIN6-Pad21)") (class "Default")
      (node (ref "SIMBLEE") (pin "21") (pinfunction "P0.05/AIN6_21") (pintype "bidirectional"))
    )
    (net (code "65") (name "unconnected-(SIMBLEE-P0.07-Pad26)") (class "Default")
      (node (ref "SIMBLEE") (pin "26") (pinfunction "P0.07_26") (pintype "bidirectional"))
    )
    (net (code "66") (name "unconnected-(SIMBLEE-P0.08-Pad20)") (class "Default")
      (node (ref "SIMBLEE") (pin "20") (pinfunction "P0.08_20") (pintype "bidirectional"))
    )
    (net (code "67") (name "unconnected-(SIMBLEE-P0.09-Pad18)") (class "Default")
      (node (ref "SIMBLEE") (pin "18") (pinfunction "P0.09_18") (pintype "bidirectional"))
    )
    (net (code "68") (name "unconnected-(SIMBLEE-P0.10-Pad27)") (class "Default")
      (node (ref "SIMBLEE") (pin "27") (pinfunction "P0.10_27") (pintype "bidirectional"))
    )
    (net (code "69") (name "unconnected-(SIMBLEE-P0.11-Pad17)") (class "Default")
      (node (ref "SIMBLEE") (pin "17") (pinfunction "P0.11_17") (pintype "bidirectional"))
    )
    (net (code "70") (name "unconnected-(SIMBLEE-P0.12-Pad16)") (class "Default")
      (node (ref "SIMBLEE") (pin "16") (pinfunction "P0.12_16") (pintype "bidirectional"))
    )
    (net (code "71") (name "unconnected-(SIMBLEE-P0.15-Pad15)") (class "Default")
      (node (ref "SIMBLEE") (pin "15") (pinfunction "P0.15_15") (pintype "bidirectional"))
    )
    (net (code "72") (name "unconnected-(SIMBLEE-P0.16-Pad14)") (class "Default")
      (node (ref "SIMBLEE") (pin "14") (pinfunction "P0.16_14") (pintype "bidirectional"))
    )
    (net (code "73") (name "unconnected-(SIMBLEE-P0.17-Pad12)") (class "Default")
      (node (ref "SIMBLEE") (pin "12") (pinfunction "P0.17_12") (pintype "bidirectional"))
    )
    (net (code "74") (name "unconnected-(SIMBLEE-P0.18-Pad13)") (class "Default")
      (node (ref "SIMBLEE") (pin "13") (pinfunction "P0.18_13") (pintype "bidirectional"))
    )
    (net (code "75") (name "unconnected-(SIMBLEE-P0.19-Pad11)") (class "Default")
      (node (ref "SIMBLEE") (pin "11") (pinfunction "P0.19_11") (pintype "bidirectional"))
    )
    (net (code "76") (name "unconnected-(SIMBLEE-P0.21-Pad36)") (class "Default")
      (node (ref "SIMBLEE") (pin "36") (pinfunction "P0.21_36") (pintype "bidirectional"))
    )
    (net (code "77") (name "unconnected-(SIMBLEE-P0.22-Pad37)") (class "Default")
      (node (ref "SIMBLEE") (pin "37") (pinfunction "P0.22_37") (pintype "bidirectional"))
    )
    (net (code "78") (name "unconnected-(SIMBLEE-P0.25-Pad38)") (class "Default")
      (node (ref "SIMBLEE") (pin "38") (pinfunction "P0.25_38") (pintype "bidirectional"))
    )
    (net (code "79") (name "unconnected-(SIMBLEE-P0.28-Pad39)") (class "Default")
      (node (ref "SIMBLEE") (pin "39") (pinfunction "P0.28_39") (pintype "bidirectional"))
    )
    (net (code "80") (name "unconnected-(SIMBLEE-P0.29-Pad40)") (class "Default")
      (node (ref "SIMBLEE") (pin "40") (pinfunction "P0.29_40") (pintype "bidirectional"))
    )
    (net (code "81") (name "unconnected-(SIMBLEE-P0.30-Pad41)") (class "Default")
      (node (ref "SIMBLEE") (pin "41") (pinfunction "P0.30_41") (pintype "bidirectional"))
    )
    (net (code "82") (name "unconnected-(TRIGGER-N.C-Pad1)") (class "Default")
      (node (ref "TRIGGER") (pin "1") (pinfunction "N.C_1") (pintype "no_connect"))
    )
    (net (code "83") (name "~{I2C-INT}") (class "Default")
      (node (ref "ATMEGA328P") (pin "32") (pinfunction "PD2(INT0)_32") (pintype "bidirectional"))
      (node (ref "INVERTER") (pin "4") (pinfunction "Y_4") (pintype "bidirectional"))
      (node (ref "SIMBLEE") (pin "24") (pinfunction "P0.02/AIN3_24") (pintype "bidirectional"))
    )
    (net (code "84") (name "~{RESET}") (class "Default")
      (node (ref "ATMEGA328P") (pin "25") (pinfunction "PC2(ADC2)_25") (pintype "bidirectional"))
      (node (ref "C2") (pin "2") (pinfunction "2_2") (pintype "passive"))
      (node (ref "R1") (pin "1") (pinfunction "1_1") (pintype "passive"))
      (node (ref "SIMBLEE") (pin "8") (pinfunction "~{RESET}_8") (pintype "input"))
    )
  )
)
